# JTAG.net
KiCad netlist of a schematic drawn in Altium Designer
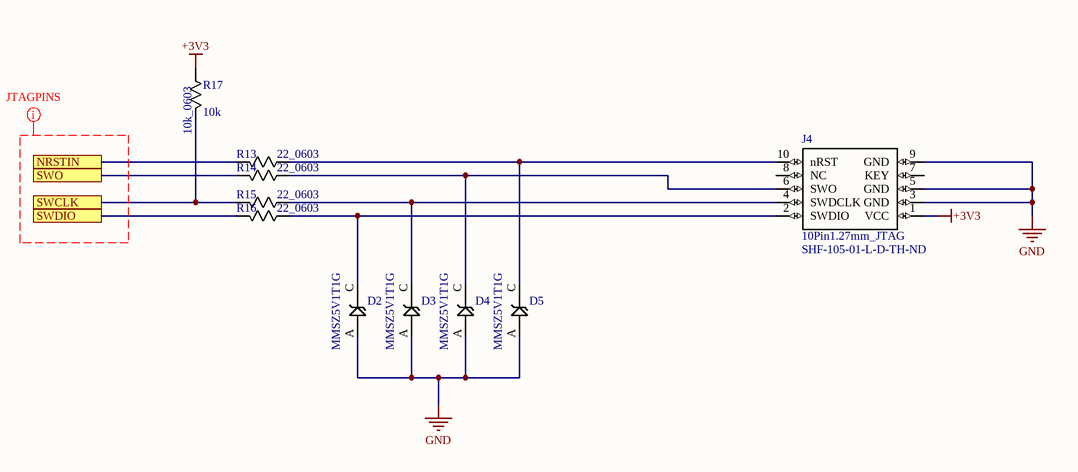
[diagram p0: JTAG.SchDoc]

(export (version "E")
  (design (tool "Eeschema 10.0.6"))
  (components
    (comp (ref "D2")
      (value "MMSZ5V1T1G")
      (footprint "SOIC127P370X94-2N")
      (description "DIODE Zener 5.1V 500mw")
      (fields (field (name "MANUFACTURER") "ON Semiconductor") (field (name "TOLERANCE") "5%"))
      (libsource (lib "Diodes") (part "MMSZ5V1T1G"))
    )
    (comp (ref "D3")
      (value "MMSZ5V1T1G")
      (footprint "SOIC127P370X94-2N")
      (description "DIODE Zener 5.1V 500mw")
      (fields (field (name "MANUFACTURER") "ON Semiconductor") (field (name "TOLERANCE") "5%"))
      (libsource (lib "Diodes") (part "MMSZ5V1T1G"))
    )
    (comp (ref "D4")
      (value "MMSZ5V1T1G")
      (footprint "SOIC127P370X94-2N")
      (description "DIODE Zener 5.1V 500mw")
      (fields (field (name "MANUFACTURER") "ON Semiconductor") (field (name "TOLERANCE") "5%"))
      (libsource (lib "Diodes") (part "MMSZ5V1T1G"))
    )
    (comp (ref "D5")
      (value "MMSZ5V1T1G")
      (footprint "SOIC127P370X94-2N")
      (description "DIODE Zener 5.1V 500mw")
      (fields (field (name "MANUFACTURER") "ON Semiconductor") (field (name "TOLERANCE") "5%"))
      (libsource (lib "Diodes") (part "MMSZ5V1T1G"))
    )
    (comp (ref "J4")
      (value "10Pin1.27mm_JTAG")
      (footprint "10Pin1.27mm")
      (fields
        (field (name "MANUFACTURER") "Samtec")
        (field (name "MANUFACTURER PART NUMBER") "SHF-105-01-L-D-TH")
        (field (name "SUPPLIER PART NUMBER 1") "SHF-105-01-L-D-TH-ND")
      )
      (libsource (lib "Connectors") (part "10Pin1.27mm_JTAG"))
    )
    (comp (ref "R13")
      (value "22_0603")
      (footprint "0603")
      (fields
        (field (name "MANUFACTURER") "Vishay")
        (field (name "MANUFACTURER PART NUMBER") "CRCW060322R0FKEA")
        (field (name "TOLERANCE") "1%")
      )
      (libsource (lib "Resistors") (part "22_0603"))
    )
    (comp (ref "R14")
      (value "22_0603")
      (footprint "0603")
      (fields
        (field (name "MANUFACTURER") "Vishay")
        (field (name "MANUFACTURER PART NUMBER") "CRCW060322R0FKEA")
        (field (name "TOLERANCE") "1%")
      )
      (libsource (lib "Resistors") (part "22_0603"))
    )
    (comp (ref "R15")
      (value "22_0603")
      (footprint "0603")
      (fields
        (field (name "MANUFACTURER") "Vishay")
        (field (name "MANUFACTURER PART NUMBER") "CRCW060322R0FKEA")
        (field (name "TOLERANCE") "1%")
      )
      (libsource (lib "Resistors") (part "22_0603"))
    )
    (comp (ref "R16")
      (value "22_0603")
      (footprint "0603")
      (fields
        (field (name "MANUFACTURER") "Vishay")
        (field (name "MANUFACTURER PART NUMBER") "CRCW060322R0FKEA")
        (field (name "TOLERANCE") "1%")
      )
      (libsource (lib "Resistors") (part "22_0603"))
    )
    (comp (ref "R17")
      (value "10k_0603")
      (footprint "0603")
      (fields
        (field (name "MANUFACTURER") "Panasonic")
        (field (name "MANUFACTURER PART NUMBER") "ERJ-3EKF1002V")
        (field (name "TOLERANCE") "1%")
        (field (name "RESISTANCE") "10k")
      )
      (libsource (lib "Resistors") (part "10k_0603"))
    )
  )
  (nets
    (net (code "1") (name "+3V3") (class "Default")
      (node (ref "J4") (pin "1") (pinfunction "VCC_1") (pintype "bidirectional"))
      (node (ref "R17") (pin "2") (pinfunction "2_2") (pintype "passive"))
    )
    (net (code "2") (name "/NRSTIN") (class "Default")
      (node (ref "R13") (pin "1") (pinfunction "1_1") (pintype "passive"))
    )
    (net (code "3") (name "/SWCLK") (class "Default")
      (node (ref "R15") (pin "1") (pinfunction "1_1") (pintype "passive"))
      (node (ref "R17") (pin "1") (pinfunction "1_1") (pintype "passive"))
    )
    (net (code "4") (name "/SWDIO") (class "Default")
      (node (ref "R16") (pin "1") (pinfunction "1_1") (pintype "passive"))
    )
    (net (code "5") (name "/SWO") (class "Default")
      (node (ref "R14") (pin "1") (pinfunction "1_1") (pintype "passive"))
    )
    (net (code "6") (name "GND") (class "Default")
      (node (ref "D2") (pin "A") (pintype "passive"))
      (node (ref "D3") (pin "A") (pintype "passive"))
      (node (ref "D4") (pin "A") (pintype "passive"))
      (node (ref "D5") (pin "A") (pintype "passive"))
      (node (ref "J4") (pin "3") (pinfunction "GND_3") (pintype "bidirectional"))
      (node (ref "J4") (pin "5") (pinfunction "GND_5") (pintype "bidirectional"))
      (node (ref "J4") (pin "9") (pinfunction "GND_9") (pintype "bidirectional"))
    )
    (net (code "7") (name "Net-(J4-SWDCLK)") (class "Default")
      (node (ref "D3") (pin "C") (pintype "passive"))
      (node (ref "J4") (pin "4") (pinfunction "SWDCLK_4") (pintype "bidirectional"))
      (node (ref "R15") (pin "2") (pinfunction "2_2") (pintype "passive"))
    )
    (net (code "8") (name "Net-(J4-SWDIO)") (class "Default")
      (node (ref "D2") (pin "C") (pintype "passive"))
      (node (ref "J4") (pin "2") (pinfunction "SWDIO_2") (pintype "bidirectional"))
      (node (ref "R16") (pin "2") (pinfunction "2_2") (pintype "passive"))
    )
    (net (code "9") (name "Net-(J4-SWO)") (class "Default")
      (node (ref "D4") (pin "C") (pintype "passive"))
      (node (ref "J4") (pin "6") (pinfunction "SWO_6") (pintype "bidirectional"))
      (node (ref "R14") (pin "2") (pinfunction "2_2") (pintype "passive"))
    )
    (net (code "10") (name "Net-(J4-nRST)") (class "Default")
      (node (ref "D5") (pin "C") (pintype "passive"))
      (node (ref "J4") (pin "10") (pinfunction "nRST_10") (pintype "bidirectional"))
      (node (ref "R13") (pin "2") (pinfunction "2_2") (pintype "passive"))
    )
    (net (code "11") (name "unconnected-(J4-KEY-Pad7)") (class "Default")
      (node (ref "J4") (pin "7") (pinfunction "KEY_7") (pintype "bidirectional"))
    )
    (net (code "12") (name "unconnected-(J4-NC-Pad8)") (class "Default")
      (node (ref "J4") (pin "8") (pinfunction "NC_8") (pintype "bidirectional"))
    )
  )
)
